# BtSolarMonitor.net
KiCad netlist of a schematic drawn in EAGLE
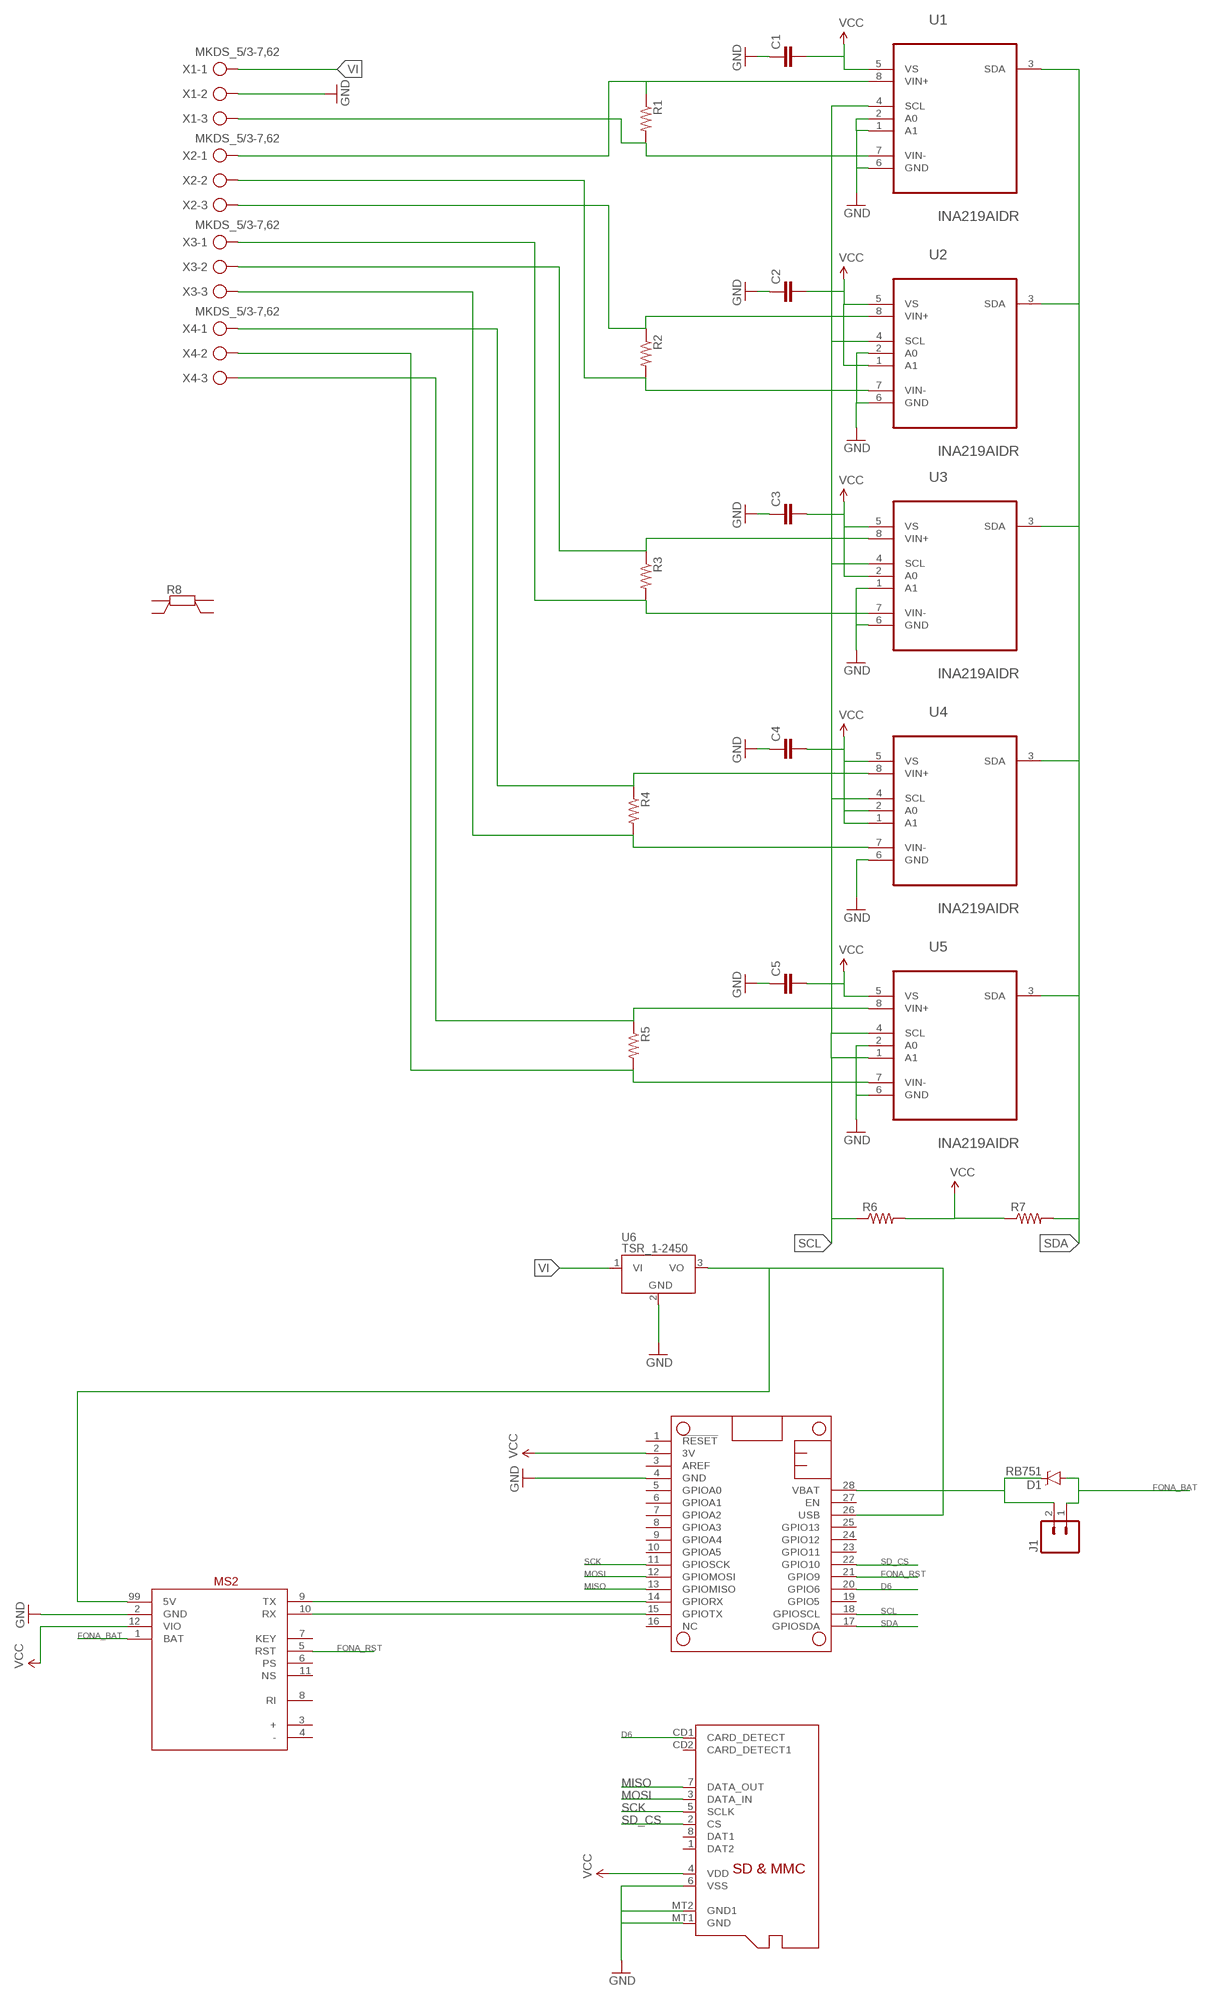
[diagram p0: schematic, sheet 1]

(export (version "E")
  (design (tool "Eeschema 10.0.6"))
  (components
    (comp (ref "C1")
      (value "CAP0805")
      (footprint "eagle-import:0805")
      (libsource (lib "eagle-import") (part "CAP0805"))
    )
    (comp (ref "C2")
      (value "CAP0805")
      (footprint "eagle-import:0805")
      (libsource (lib "eagle-import") (part "CAP0805"))
    )
    (comp (ref "C3")
      (value "CAP0805")
      (footprint "eagle-import:0805")
      (libsource (lib "eagle-import") (part "CAP0805"))
    )
    (comp (ref "C4")
      (value "CAP0805")
      (footprint "eagle-import:0805")
      (libsource (lib "eagle-import") (part "CAP0805"))
    )
    (comp (ref "C5")
      (value "CAP0805")
      (footprint "eagle-import:0805")
      (libsource (lib "eagle-import") (part "CAP0805"))
    )
    (comp (ref "D1")
      (value "RB751")
      (footprint "eagle-import:SOD-523")
      (libsource (lib "eagle-import") (part "DIODE-SCHOTTKY-RB751"))
    )
    (comp (ref "J1")
      (value "M02PTH")
      (footprint "eagle-import:1X02")
      (libsource (lib "eagle-import") (part "M02PTH"))
    )
    (comp (ref "MS1")
      (value "FEATHERWING")
      (footprint "eagle-import:FEATHERWING")
      (libsource (lib "eagle-import") (part "FEATHERWING"))
    )
    (comp (ref "MS2")
      (value "FONA")
      (footprint "eagle-import:FONA")
      (libsource (lib "eagle-import") (part "FONA"))
    )
    (comp (ref "R1")
      (value "R-US_R2512")
      (footprint "eagle-import:R2512")
      (libsource (lib "eagle-import") (part "R-US_R2512"))
    )
    (comp (ref "R2")
      (value "R-US_R2512")
      (footprint "eagle-import:R2512")
      (libsource (lib "eagle-import") (part "R-US_R2512"))
    )
    (comp (ref "R3")
      (value "R-US_R2512")
      (footprint "eagle-import:R2512")
      (libsource (lib "eagle-import") (part "R-US_R2512"))
    )
    (comp (ref "R4")
      (value "R-US_R2512")
      (footprint "eagle-import:R2512")
      (libsource (lib "eagle-import") (part "R-US_R2512"))
    )
    (comp (ref "R5")
      (value "R-US_R2512")
      (footprint "eagle-import:R2512")
      (libsource (lib "eagle-import") (part "R-US_R2512"))
    )
    (comp (ref "R6")
      (value "RESISTOR0805-RES")
      (footprint "eagle-import:0805")
      (libsource (lib "eagle-import") (part "RESISTOR0805-RES"))
    )
    (comp (ref "R7")
      (value "RESISTOR0805-RES")
      (footprint "eagle-import:0805")
      (libsource (lib "eagle-import") (part "RESISTOR0805-RES"))
    )
    (comp (ref "R8")
      (value "SMV")
      (footprint "eagle-import:SMV")
      (libsource (lib "eagle-import") (part "SMV"))
    )
    (comp (ref "U$1")
      (value "MICROSD")
      (footprint "eagle-import:MICROSD")
      (libsource (lib "eagle-import") (part "MICROSD"))
    )
    (comp (ref "U1")
      (value "INA219AIDR")
      (footprint "eagle-import:SOIC127P600X175-8N")
      (libsource (lib "eagle-import") (part "INA219AIDR"))
    )
    (comp (ref "U2")
      (value "INA219AIDR")
      (footprint "eagle-import:SOIC127P600X175-8N")
      (libsource (lib "eagle-import") (part "INA219AIDR"))
    )
    (comp (ref "U3")
      (value "INA219AIDR")
      (footprint "eagle-import:SOIC127P600X175-8N")
      (libsource (lib "eagle-import") (part "INA219AIDR"))
    )
    (comp (ref "U4")
      (value "INA219AIDR")
      (footprint "eagle-import:SOIC127P600X175-8N")
      (libsource (lib "eagle-import") (part "INA219AIDR"))
    )
    (comp (ref "U5")
      (value "INA219AIDR")
      (footprint "eagle-import:SOIC127P600X175-8N")
      (libsource (lib "eagle-import") (part "INA219AIDR"))
    )
    (comp (ref "U6")
      (value "TSR_1-2450")
      (footprint "eagle-import:TSR-1")
      (libsource (lib "eagle-import") (part "TSR_1-2450"))
    )
    (comp (ref "X1")
      (value "MKDS_5/3-7,62")
      (footprint "eagle-import:MKDS_5_3-762")
      (libsource (lib "eagle-import") (part "MKDS_5/3-7,62"))
    )
    (comp (ref "X2")
      (value "MKDS_5/3-7,62")
      (footprint "eagle-import:MKDS_5_3-762")
      (libsource (lib "eagle-import") (part "MKDS_5/3-7,62"))
    )
    (comp (ref "X3")
      (value "MKDS_5/3-7,62")
      (footprint "eagle-import:MKDS_5_3-762")
      (libsource (lib "eagle-import") (part "MKDS_5/3-7,62"))
    )
    (comp (ref "X4")
      (value "MKDS_5/3-7,62")
      (footprint "eagle-import:MKDS_5_3-762")
      (libsource (lib "eagle-import") (part "MKDS_5/3-7,62"))
    )
  )
  (nets
    (net (code "1") (name "/D6") (class "Default")
      (node (ref "MS1") (pin "20") (pinfunction "GPIO6_20") (pintype "bidirectional"))
      (node (ref "U$1") (pin "CD1") (pinfunction "CARD_DETECT_CD1") (pintype "passive"))
    )
    (net (code "2") (name "/FONA_BAT") (class "Default")
      (node (ref "D1") (pin "A") (pinfunction "A_A") (pintype "passive"))
      (node (ref "J1") (pin "1") (pinfunction "1_1") (pintype "passive"))
      (node (ref "MS2") (pin "1") (pinfunction "BAT_1") (pintype "bidirectional"))
    )
    (net (code "3") (name "/FONA_RST") (class "Default")
      (node (ref "MS1") (pin "21") (pinfunction "GPIO9_21") (pintype "bidirectional"))
      (node (ref "MS2") (pin "5") (pinfunction "RST_5") (pintype "bidirectional"))
    )
    (net (code "4") (name "/MISO") (class "Default")
      (node (ref "MS1") (pin "13") (pinfunction "GPIOMISO_13") (pintype "bidirectional"))
      (node (ref "U$1") (pin "7") (pinfunction "DATA_OUT_7") (pintype "output"))
    )
    (net (code "5") (name "/MOSI") (class "Default")
      (node (ref "MS1") (pin "12") (pinfunction "GPIOMOSI_12") (pintype "bidirectional"))
      (node (ref "U$1") (pin "3") (pinfunction "DATA_IN_3") (pintype "input"))
    )
    (net (code "6") (name "/SCK") (class "Default")
      (node (ref "MS1") (pin "11") (pinfunction "GPIOSCK_11") (pintype "bidirectional"))
      (node (ref "U$1") (pin "5") (pinfunction "SCLK_5") (pintype "input"))
    )
    (net (code "7") (name "/SD_CS") (class "Default")
      (node (ref "MS1") (pin "22") (pinfunction "GPIO10_22") (pintype "bidirectional"))
      (node (ref "U$1") (pin "2") (pinfunction "CS_2") (pintype "input"))
    )
    (net (code "8") (name "GND") (class "Default")
      (node (ref "C1") (pin "1") (pinfunction "1_1") (pintype "passive"))
      (node (ref "C2") (pin "1") (pinfunction "1_1") (pintype "passive"))
      (node (ref "C3") (pin "1") (pinfunction "1_1") (pintype "passive"))
      (node (ref "C4") (pin "1") (pinfunction "1_1") (pintype "passive"))
      (node (ref "C5") (pin "1") (pinfunction "1_1") (pintype "passive"))
      (node (ref "MS1") (pin "4") (pinfunction "GND_4") (pintype "power_in"))
      (node (ref "MS2") (pin "2") (pinfunction "GND_2") (pintype "bidirectional"))
      (node (ref "U$1") (pin "6") (pinfunction "VSS_6") (pintype "power_in"))
      (node (ref "U$1") (pin "MT1") (pinfunction "GND_MT1") (pintype "power_in"))
      (node (ref "U$1") (pin "MT2") (pinfunction "GND1_MT2") (pintype "power_in"))
      (node (ref "U1") (pin "1") (pinfunction "A1_1") (pintype "input"))
      (node (ref "U1") (pin "2") (pinfunction "A0_2") (pintype "input"))
      (node (ref "U1") (pin "6") (pinfunction "GND_6") (pintype "passive"))
      (node (ref "U2") (pin "2") (pinfunction "A0_2") (pintype "input"))
      (node (ref "U2") (pin "6") (pinfunction "GND_6") (pintype "passive"))
      (node (ref "U3") (pin "1") (pinfunction "A1_1") (pintype "input"))
      (node (ref "U3") (pin "6") (pinfunction "GND_6") (pintype "passive"))
      (node (ref "U4") (pin "6") (pinfunction "GND_6") (pintype "passive"))
      (node (ref "U5") (pin "2") (pinfunction "A0_2") (pintype "input"))
      (node (ref "U5") (pin "6") (pinfunction "GND_6") (pintype "passive"))
      (node (ref "U6") (pin "2") (pinfunction "GND_2") (pintype "power_in"))
      (node (ref "X1") (pin "2") (pinfunction "KL_2") (pintype "passive"))
    )
    (net (code "9") (name "Net-(MS1-GPIORX)") (class "Default")
      (node (ref "MS1") (pin "14") (pinfunction "GPIORX_14") (pintype "bidirectional"))
      (node (ref "MS2") (pin "9") (pinfunction "TX_9") (pintype "bidirectional"))
    )
    (net (code "10") (name "Net-(MS1-GPIOTX)") (class "Default")
      (node (ref "MS1") (pin "15") (pinfunction "GPIOTX_15") (pintype "bidirectional"))
      (node (ref "MS2") (pin "10") (pinfunction "RX_10") (pintype "bidirectional"))
    )
    (net (code "11") (name "Net-(MS1-USB)") (class "Default")
      (node (ref "MS1") (pin "26") (pinfunction "USB_26") (pintype "power_in"))
      (node (ref "MS2") (pin "99") (pinfunction "5V_99") (pintype "bidirectional"))
      (node (ref "U6") (pin "3") (pinfunction "VO_3") (pintype "power_in"))
    )
    (net (code "12") (name "Net-(MS1-VBAT)") (class "Default")
      (node (ref "D1") (pin "C") (pinfunction "C_C") (pintype "passive"))
      (node (ref "J1") (pin "2") (pinfunction "2_2") (pintype "passive"))
      (node (ref "MS1") (pin "28") (pinfunction "VBAT_28") (pintype "power_in"))
    )
    (net (code "13") (name "Net-(U1-VIN+)") (class "Default")
      (node (ref "R1") (pin "1") (pinfunction "1_1") (pintype "passive"))
      (node (ref "U1") (pin "8") (pinfunction "VIN+_8") (pintype "power_in"))
      (node (ref "X2") (pin "1") (pinfunction "KL_1") (pintype "passive"))
    )
    (net (code "14") (name "Net-(U1-VIN-)") (class "Default")
      (node (ref "R1") (pin "2") (pinfunction "2_2") (pintype "passive"))
      (node (ref "U1") (pin "7") (pinfunction "VIN-_7") (pintype "power_in"))
      (node (ref "X1") (pin "3") (pinfunction "KL_3") (pintype "passive"))
    )
    (net (code "15") (name "Net-(U2-VIN+)") (class "Default")
      (node (ref "R2") (pin "1") (pinfunction "1_1") (pintype "passive"))
      (node (ref "U2") (pin "8") (pinfunction "VIN+_8") (pintype "power_in"))
      (node (ref "X2") (pin "3") (pinfunction "KL_3") (pintype "passive"))
    )
    (net (code "16") (name "Net-(U2-VIN-)") (class "Default")
      (node (ref "R2") (pin "2") (pinfunction "2_2") (pintype "passive"))
      (node (ref "U2") (pin "7") (pinfunction "VIN-_7") (pintype "power_in"))
      (node (ref "X2") (pin "2") (pinfunction "KL_2") (pintype "passive"))
    )
    (net (code "17") (name "Net-(U3-VIN+)") (class "Default")
      (node (ref "R3") (pin "1") (pinfunction "1_1") (pintype "passive"))
      (node (ref "U3") (pin "8") (pinfunction "VIN+_8") (pintype "power_in"))
      (node (ref "X3") (pin "2") (pinfunction "KL_2") (pintype "passive"))
    )
    (net (code "18") (name "Net-(U3-VIN-)") (class "Default")
      (node (ref "R3") (pin "2") (pinfunction "2_2") (pintype "passive"))
      (node (ref "U3") (pin "7") (pinfunction "VIN-_7") (pintype "power_in"))
      (node (ref "X3") (pin "1") (pinfunction "KL_1") (pintype "passive"))
    )
    (net (code "19") (name "Net-(U4-VIN+)") (class "Default")
      (node (ref "R4") (pin "1") (pinfunction "1_1") (pintype "passive"))
      (node (ref "U4") (pin "8") (pinfunction "VIN+_8") (pintype "power_in"))
      (node (ref "X4") (pin "1") (pinfunction "KL_1") (pintype "passive"))
    )
    (net (code "20") (name "Net-(U4-VIN-)") (class "Default")
      (node (ref "R4") (pin "2") (pinfunction "2_2") (pintype "passive"))
      (node (ref "U4") (pin "7") (pinfunction "VIN-_7") (pintype "power_in"))
      (node (ref "X3") (pin "3") (pinfunction "KL_3") (pintype "passive"))
    )
    (net (code "21") (name "Net-(U5-VIN+)") (class "Default")
      (node (ref "R5") (pin "1") (pinfunction "1_1") (pintype "passive"))
      (node (ref "U5") (pin "8") (pinfunction "VIN+_8") (pintype "power_in"))
      (node (ref "X4") (pin "3") (pinfunction "KL_3") (pintype "passive"))
    )
    (net (code "22") (name "Net-(U5-VIN-)") (class "Default")
      (node (ref "R5") (pin "2") (pinfunction "2_2") (pintype "passive"))
      (node (ref "U5") (pin "7") (pinfunction "VIN-_7") (pintype "power_in"))
      (node (ref "X4") (pin "2") (pinfunction "KL_2") (pintype "passive"))
    )
    (net (code "23") (name "SCL") (class "Default")
      (node (ref "MS1") (pin "18") (pinfunction "GPIOSCL_18") (pintype "bidirectional"))
      (node (ref "R6") (pin "1") (pinfunction "1_1") (pintype "passive"))
      (node (ref "U1") (pin "4") (pinfunction "SCL_4") (pintype "input"))
      (node (ref "U2") (pin "4") (pinfunction "SCL_4") (pintype "input"))
      (node (ref "U3") (pin "4") (pinfunction "SCL_4") (pintype "input"))
      (node (ref "U4") (pin "4") (pinfunction "SCL_4") (pintype "input"))
      (node (ref "U5") (pin "1") (pinfunction "A1_1") (pintype "input"))
      (node (ref "U5") (pin "4") (pinfunction "SCL_4") (pintype "input"))
    )
    (net (code "24") (name "SDA") (class "Default")
      (node (ref "MS1") (pin "17") (pinfunction "GPIOSDA_17") (pintype "bidirectional"))
      (node (ref "R7") (pin "2") (pinfunction "2_2") (pintype "passive"))
      (node (ref "U1") (pin "3") (pinfunction "SDA_3") (pintype "bidirectional"))
      (node (ref "U2") (pin "3") (pinfunction "SDA_3") (pintype "bidirectional"))
      (node (ref "U3") (pin "3") (pinfunction "SDA_3") (pintype "bidirectional"))
      (node (ref "U4") (pin "3") (pinfunction "SDA_3") (pintype "bidirectional"))
      (node (ref "U5") (pin "3") (pinfunction "SDA_3") (pintype "bidirectional"))
    )
    (net (code "25") (name "VCC") (class "Default")
      (node (ref "C1") (pin "2") (pinfunction "2_2") (pintype "passive"))
      (node (ref "C2") (pin "2") (pinfunction "2_2") (pintype "passive"))
      (node (ref "C3") (pin "2") (pinfunction "2_2") (pintype "passive"))
      (node (ref "C4") (pin "2") (pinfunction "2_2") (pintype "passive"))
      (node (ref "C5") (pin "2") (pinfunction "2_2") (pintype "passive"))
      (node (ref "MS1") (pin "2") (pinfunction "3V_2") (pintype "power_in"))
      (node (ref "MS2") (pin "12") (pinfunction "VIO_12") (pintype "bidirectional"))
      (node (ref "R6") (pin "2") (pinfunction "2_2") (pintype "passive"))
      (node (ref "R7") (pin "1") (pinfunction "1_1") (pintype "passive"))
      (node (ref "U$1") (pin "4") (pinfunction "VDD_4") (pintype "power_in"))
      (node (ref "U1") (pin "5") (pinfunction "VS_5") (pintype "power_in"))
      (node (ref "U2") (pin "1") (pinfunction "A1_1") (pintype "input"))
      (node (ref "U2") (pin "5") (pinfunction "VS_5") (pintype "power_in"))
      (node (ref "U3") (pin "2") (pinfunction "A0_2") (pintype "input"))
      (node (ref "U3") (pin "5") (pinfunction "VS_5") (pintype "power_in"))
      (node (ref "U4") (pin "1") (pinfunction "A1_1") (pintype "input"))
      (node (ref "U4") (pin "2") (pinfunction "A0_2") (pintype "input"))
      (node (ref "U4") (pin "5") (pinfunction "VS_5") (pintype "power_in"))
      (node (ref "U5") (pin "5") (pinfunction "VS_5") (pintype "power_in"))
    )
    (net (code "26") (name "VI") (class "Default")
      (node (ref "U6") (pin "1") (pinfunction "VI_1") (pintype "power_in"))
      (node (ref "X1") (pin "1") (pinfunction "KL_1") (pintype "passive"))
    )
    (net (code "27") (name "unconnected-(MS1-AREF-Pad3)") (class "Default")
      (node (ref "MS1") (pin "3") (pinfunction "AREF_3") (pintype "passive"))
    )
    (net (code "28") (name "unconnected-(MS1-EN-Pad27)") (class "Default")
      (node (ref "MS1") (pin "27") (pinfunction "EN_27") (pintype "passive"))
    )
    (net (code "29") (name "unconnected-(MS1-GPIO5-Pad19)") (class "Default")
      (node (ref "MS1") (pin "19") (pinfunction "GPIO5_19") (pintype "bidirectional"))
    )
    (net (code "30") (name "unconnected-(MS1-GPIO11-Pad23)") (class "Default")
      (node (ref "MS1") (pin "23") (pinfunction "GPIO11_23") (pintype "bidirectional"))
    )
    (net (code "31") (name "unconnected-(MS1-GPIO12-Pad24)") (class "Default")
      (node (ref "MS1") (pin "24") (pinfunction "GPIO12_24") (pintype "bidirectional"))
    )
    (net (code "32") (name "unconnected-(MS1-GPIO13-Pad25)") (class "Default")
      (node (ref "MS1") (pin "25") (pinfunction "GPIO13_25") (pintype "bidirectional"))
    )
    (net (code "33") (name "unconnected-(MS1-GPIOA0-Pad5)") (class "Default")
      (node (ref "MS1") (pin "5") (pinfunction "GPIOA0_5") (pintype "bidirectional"))
    )
    (net (code "34") (name "unconnected-(MS1-GPIOA1-Pad6)") (class "Default")
      (node (ref "MS1") (pin "6") (pinfunction "GPIOA1_6") (pintype "bidirectional"))
    )
    (net (code "35") (name "unconnected-(MS1-GPIOA2-Pad7)") (class "Default")
      (node (ref "MS1") (pin "7") (pinfunction "GPIOA2_7") (pintype "bidirectional"))
    )
    (net (code "36") (name "unconnected-(MS1-GPIOA3-Pad8)") (class "Default")
      (node (ref "MS1") (pin "8") (pinfunction "GPIOA3_8") (pintype "bidirectional"))
    )
    (net (code "37") (name "unconnected-(MS1-GPIOA4-Pad9)") (class "Default")
      (node (ref "MS1") (pin "9") (pinfunction "GPIOA4_9") (pintype "bidirectional"))
    )
    (net (code "38") (name "unconnected-(MS1-GPIOA5-Pad10)") (class "Default")
      (node (ref "MS1") (pin "10") (pinfunction "GPIOA5_10") (pintype "bidirectional"))
    )
    (net (code "39") (name "unconnected-(MS1-NC-Pad16)") (class "Default")
      (node (ref "MS1") (pin "16") (pinfunction "NC_16") (pintype "passive"))
    )
    (net (code "40") (name "unconnected-(MS1-~{RESET}-Pad1)") (class "Default")
      (node (ref "MS1") (pin "1") (pinfunction "~{RESET}_1") (pintype "input"))
    )
    (net (code "41") (name "unconnected-(MS2-+-Pad3)") (class "Default")
      (node (ref "MS2") (pin "3") (pinfunction "+_3") (pintype "bidirectional"))
    )
    (net (code "42") (name "unconnected-(MS2---Pad4)") (class "Default")
      (node (ref "MS2") (pin "4") (pinfunction "-_4") (pintype "bidirectional"))
    )
    (net (code "43") (name "unconnected-(MS2-KEY-Pad7)") (class "Default")
      (node (ref "MS2") (pin "7") (pinfunction "KEY_7") (pintype "bidirectional"))
    )
    (net (code "44") (name "unconnected-(MS2-NS-Pad11)") (class "Default")
      (node (ref "MS2") (pin "11") (pinfunction "NS_11") (pintype "bidirectional"))
    )
    (net (code "45") (name "unconnected-(MS2-PS-Pad6)") (class "Default")
      (node (ref "MS2") (pin "6") (pinfunction "PS_6") (pintype "bidirectional"))
    )
    (net (code "46") (name "unconnected-(MS2-RI-Pad8)") (class "Default")
      (node (ref "MS2") (pin "8") (pinfunction "RI_8") (pintype "bidirectional"))
    )
    (net (code "47") (name "unconnected-(R8-A-PadI1)") (class "Default")
      (node (ref "R8") (pin "I1") (pinfunction "A_I1") (pintype "passive"))
    )
    (net (code "48") (name "unconnected-(R8-B-PadI2)") (class "Default")
      (node (ref "R8") (pin "I2") (pinfunction "B_I2") (pintype "passive"))
    )
    (net (code "49") (name "unconnected-(R8-SA-PadU1)") (class "Default")
      (node (ref "R8") (pin "U1") (pinfunction "SA_U1") (pintype "passive"))
    )
    (net (code "50") (name "unconnected-(R8-SB-PadU2)") (class "Default")
      (node (ref "R8") (pin "U2") (pinfunction "SB_U2") (pintype "passive"))
    )
    (net (code "51") (name "unconnected-(U$1-CARD_DETECT1-PadCD2)") (class "Default")
      (node (ref "U$1") (pin "CD2") (pinfunction "CARD_DETECT1_CD2") (pintype "passive"))
    )
    (net (code "52") (name "unconnected-(U$1-DAT1-Pad8)") (class "Default")
      (node (ref "U$1") (pin "8") (pinfunction "DAT1_8") (pintype "bidirectional"))
    )
    (net (code "53") (name "unconnected-(U$1-DAT2-Pad1)") (class "Default")
      (node (ref "U$1") (pin "1") (pinfunction "DAT2_1") (pintype "bidirectional"))
    )
  )
)
